# SCH_interrupt-proof-of-concept_2025-12-1.net
KiCad netlist of a schematic drawn in EasyEDA
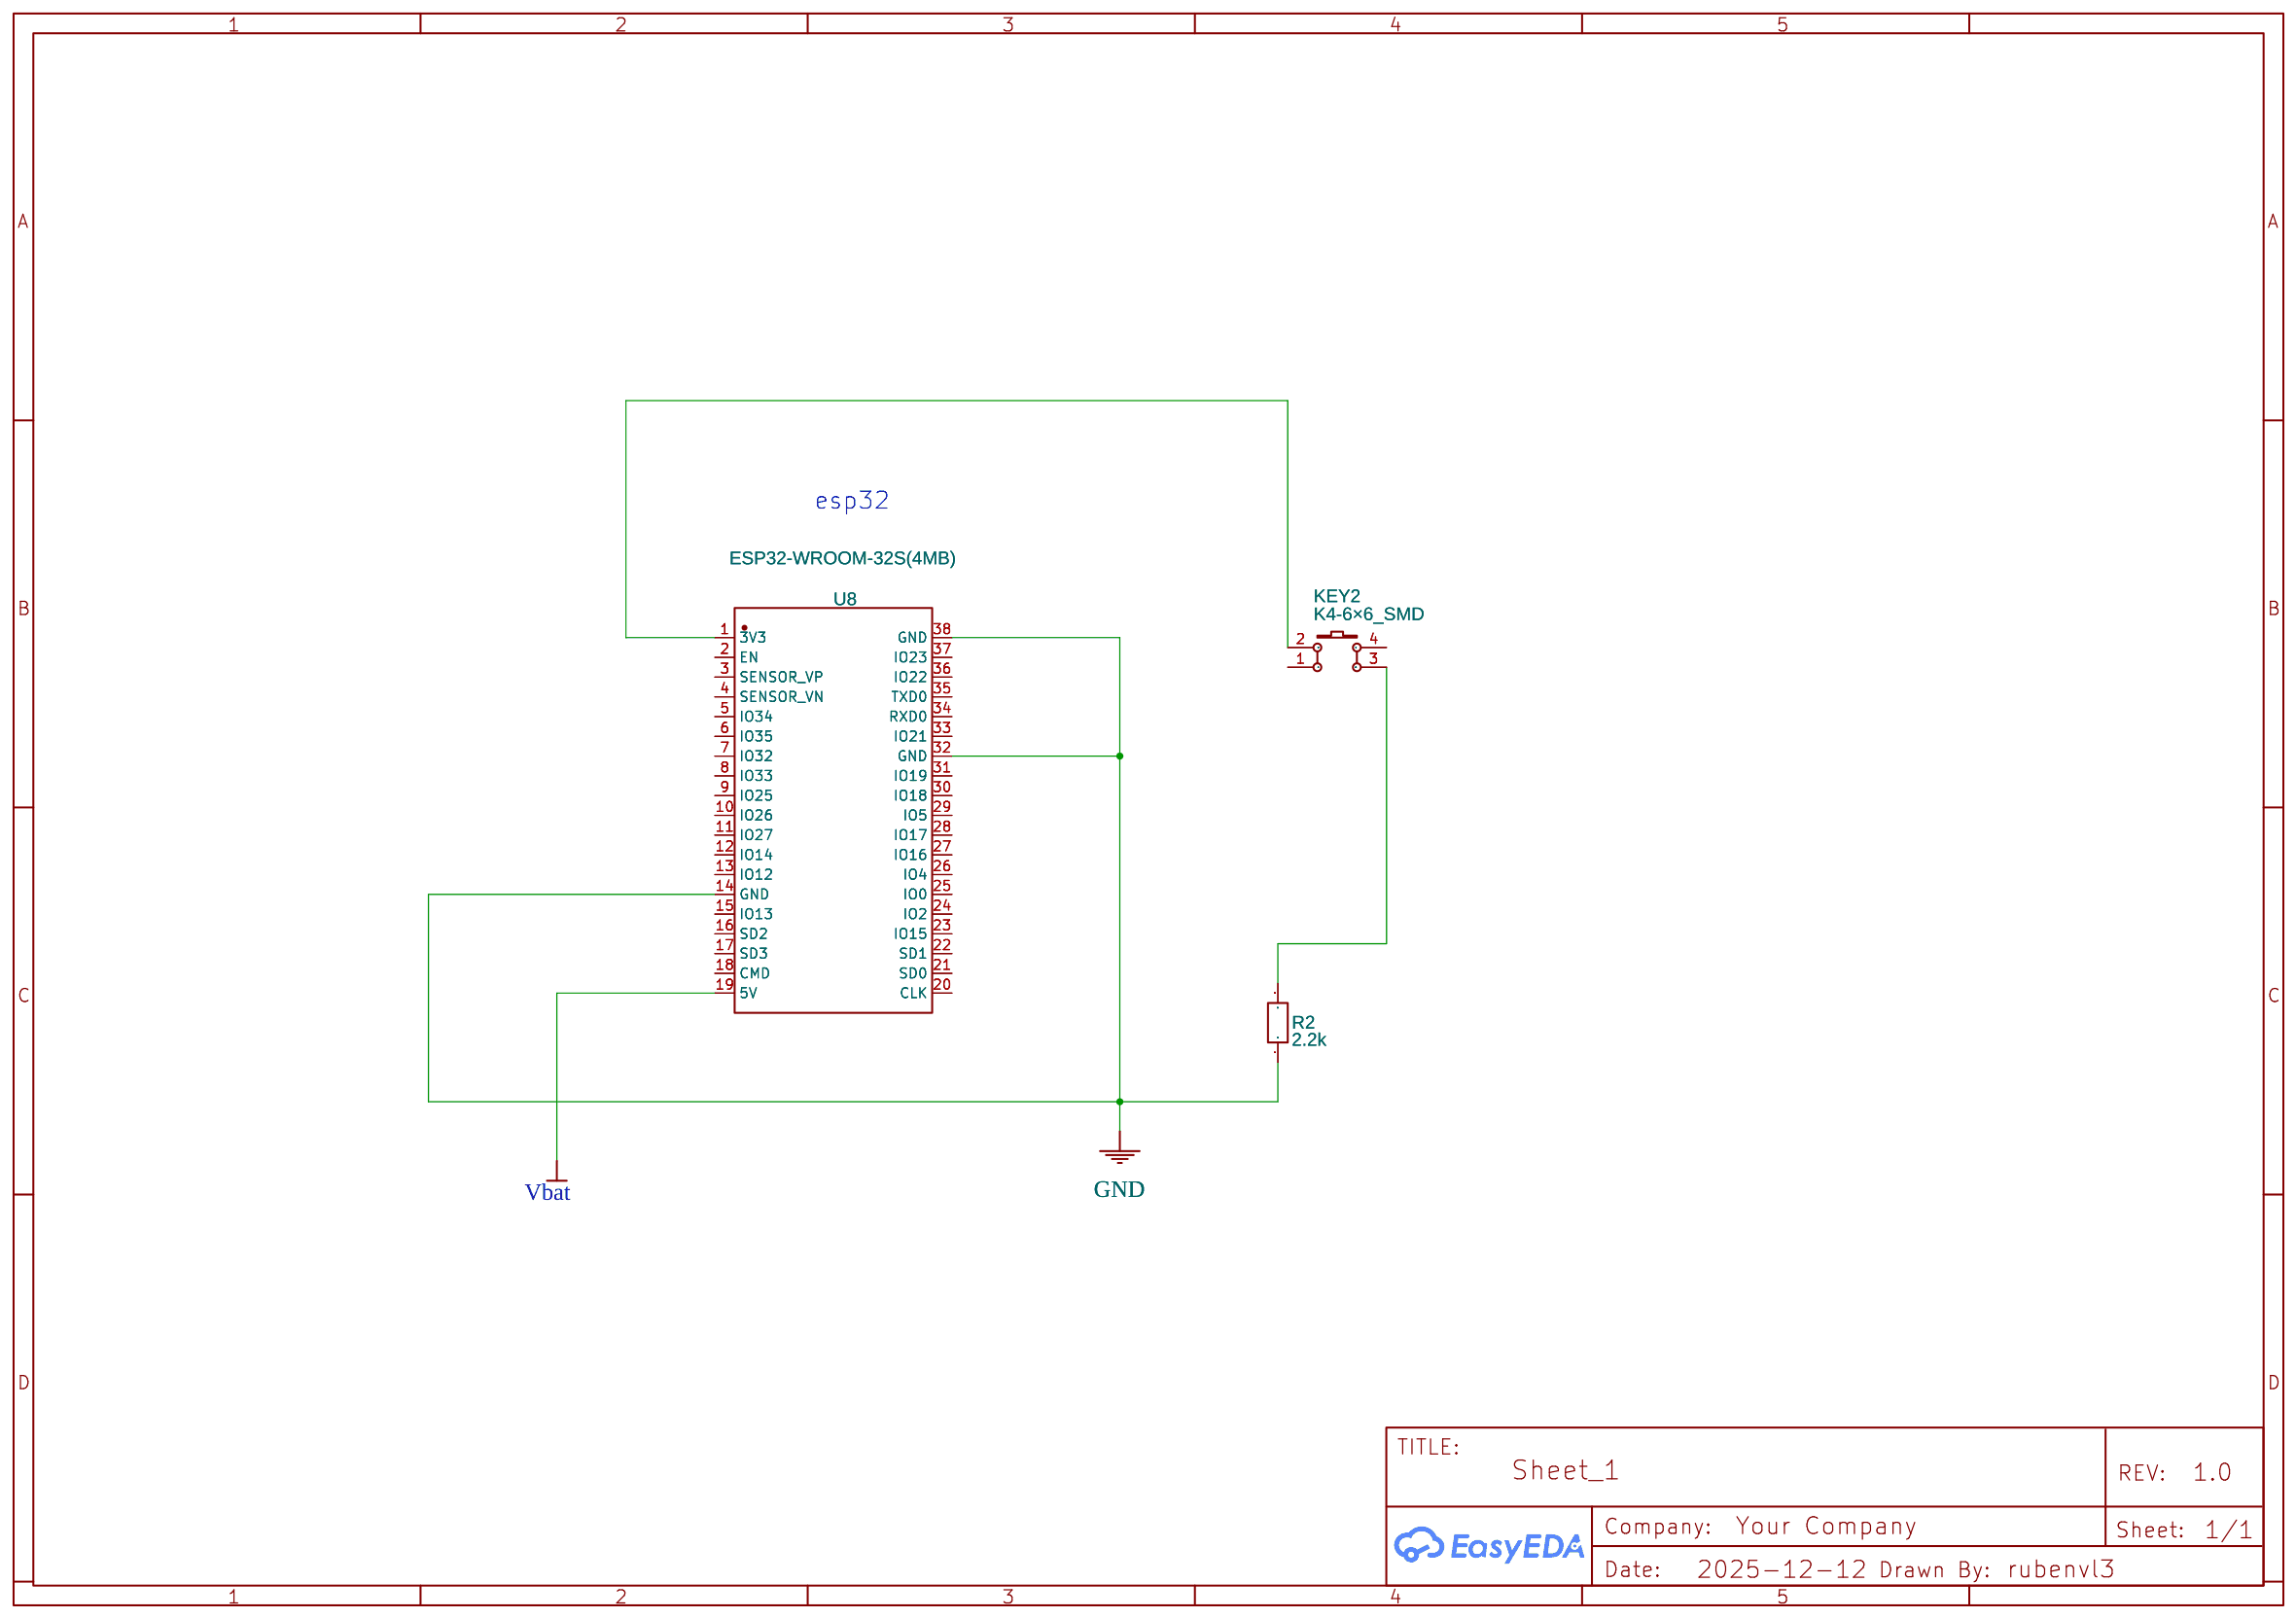
[diagram p0: schematic sheet]

(export (version "E")
  (design (tool "Eeschema 10.0.6"))
  (components
    (comp (ref "KEY2")
      (value "K4-6×6_SMD")
      (fields (field (name "Manufacturer Part") "K2-6639SP-D4SC-04") (field (name "Manufacturer") "韩国韩荣"))
      (libsource (lib "") (part "K4-6×6_SMD"))
    )
    (comp (ref "R2") (value "2.2k") (libsource (lib "") (part "R_0805_EU")))
    (comp (ref "U8")
      (value "ESP32-WROOM-32S(4MB)")
      (fields (field (name "Manufacturer") "Espressif Systems"))
      (libsource (lib "") (part "ESP32-WROOM-32S(4MB)"))
    )
  )
  (nets
    (net (code "1") (name "GND") (class "Default")
      (node (ref "R2") (pin "1") (pinfunction "1_1") (pintype "unspecified"))
      (node (ref "U8") (pin "14") (pinfunction "GND_14") (pintype "unspecified"))
      (node (ref "U8") (pin "32") (pinfunction "GND_32") (pintype "unspecified"))
      (node (ref "U8") (pin "38") (pinfunction "GND_38") (pintype "unspecified"))
    )
    (net (code "2") (name "Net-(KEY2-Pad3)") (class "Default")
      (node (ref "KEY2") (pin "3") (pinfunction "3_3") (pintype "unspecified"))
      (node (ref "R2") (pin "2") (pinfunction "2_2") (pintype "unspecified"))
    )
    (net (code "3") (name "Net-(U8-3V3)") (class "Default")
      (node (ref "KEY2") (pin "2") (pinfunction "2_2") (pintype "unspecified"))
      (node (ref "U8") (pin "1") (pinfunction "3V3_1") (pintype "unspecified"))
    )
    (net (code "4") (name "Vbat") (class "Default")
      (node (ref "U8") (pin "19") (pinfunction "5V_19") (pintype "unspecified"))
    )
    (net (code "5") (name "unconnected-(KEY2-Pad1)") (class "Default")
      (node (ref "KEY2") (pin "1") (pinfunction "1_1") (pintype "unspecified"))
    )
    (net (code "6") (name "unconnected-(KEY2-Pad4)") (class "Default")
      (node (ref "KEY2") (pin "4") (pinfunction "4_4") (pintype "unspecified"))
    )
    (net (code "7") (name "unconnected-(U8-CLK-Pad20)") (class "Default")
      (node (ref "U8") (pin "20") (pinfunction "CLK_20") (pintype "unspecified"))
    )
    (net (code "8") (name "unconnected-(U8-CMD-Pad18)") (class "Default")
      (node (ref "U8") (pin "18") (pinfunction "CMD_18") (pintype "unspecified"))
    )
    (net (code "9") (name "unconnected-(U8-EN-Pad2)") (class "Default")
      (node (ref "U8") (pin "2") (pinfunction "EN_2") (pintype "unspecified"))
    )
    (net (code "10") (name "unconnected-(U8-IO0-Pad25)") (class "Default")
      (node (ref "U8") (pin "25") (pinfunction "IO0_25") (pintype "unspecified"))
    )
    (net (code "11") (name "unconnected-(U8-IO2-Pad24)") (class "Default")
      (node (ref "U8") (pin "24") (pinfunction "IO2_24") (pintype "unspecified"))
    )
    (net (code "12") (name "unconnected-(U8-IO4-Pad26)") (class "Default")
      (node (ref "U8") (pin "26") (pinfunction "IO4_26") (pintype "unspecified"))
    )
    (net (code "13") (name "unconnected-(U8-IO5-Pad29)") (class "Default")
      (node (ref "U8") (pin "29") (pinfunction "IO5_29") (pintype "unspecified"))
    )
    (net (code "14") (name "unconnected-(U8-IO12-Pad13)") (class "Default")
      (node (ref "U8") (pin "13") (pinfunction "IO12_13") (pintype "unspecified"))
    )
    (net (code "15") (name "unconnected-(U8-IO13-Pad15)") (class "Default")
      (node (ref "U8") (pin "15") (pinfunction "IO13_15") (pintype "unspecified"))
    )
    (net (code "16") (name "unconnected-(U8-IO14-Pad12)") (class "Default")
      (node (ref "U8") (pin "12") (pinfunction "IO14_12") (pintype "unspecified"))
    )
    (net (code "17") (name "unconnected-(U8-IO15-Pad23)") (class "Default")
      (node (ref "U8") (pin "23") (pinfunction "IO15_23") (pintype "unspecified"))
    )
    (net (code "18") (name "unconnected-(U8-IO16-Pad27)") (class "Default")
      (node (ref "U8") (pin "27") (pinfunction "IO16_27") (pintype "unspecified"))
    )
    (net (code "19") (name "unconnected-(U8-IO17-Pad28)") (class "Default")
      (node (ref "U8") (pin "28") (pinfunction "IO17_28") (pintype "unspecified"))
    )
    (net (code "20") (name "unconnected-(U8-IO18-Pad30)") (class "Default")
      (node (ref "U8") (pin "30") (pinfunction "IO18_30") (pintype "unspecified"))
    )
    (net (code "21") (name "unconnected-(U8-IO19-Pad31)") (class "Default")
      (node (ref "U8") (pin "31") (pinfunction "IO19_31") (pintype "unspecified"))
    )
    (net (code "22") (name "unconnected-(U8-IO21-Pad33)") (class "Default")
      (node (ref "U8") (pin "33") (pinfunction "IO21_33") (pintype "unspecified"))
    )
    (net (code "23") (name "unconnected-(U8-IO22-Pad36)") (class "Default")
      (node (ref "U8") (pin "36") (pinfunction "IO22_36") (pintype "unspecified"))
    )
    (net (code "24") (name "unconnected-(U8-IO23-Pad37)") (class "Default")
      (node (ref "U8") (pin "37") (pinfunction "IO23_37") (pintype "unspecified"))
    )
    (net (code "25") (name "unconnected-(U8-IO25-Pad9)") (class "Default")
      (node (ref "U8") (pin "9") (pinfunction "IO25_9") (pintype "unspecified"))
    )
    (net (code "26") (name "unconnected-(U8-IO26-Pad10)") (class "Default")
      (node (ref "U8") (pin "10") (pinfunction "IO26_10") (pintype "unspecified"))
    )
    (net (code "27") (name "unconnected-(U8-IO27-Pad11)") (class "Default")
      (node (ref "U8") (pin "11") (pinfunction "IO27_11") (pintype "unspecified"))
    )
    (net (code "28") (name "unconnected-(U8-IO32-Pad7)") (class "Default")
      (node (ref "U8") (pin "7") (pinfunction "IO32_7") (pintype "unspecified"))
    )
    (net (code "29") (name "unconnected-(U8-IO33-Pad8)") (class "Default")
      (node (ref "U8") (pin "8") (pinfunction "IO33_8") (pintype "unspecified"))
    )
    (net (code "30") (name "unconnected-(U8-IO34-Pad5)") (class "Default")
      (node (ref "U8") (pin "5") (pinfunction "IO34_5") (pintype "unspecified"))
    )
    (net (code "31") (name "unconnected-(U8-IO35-Pad6)") (class "Default")
      (node (ref "U8") (pin "6") (pinfunction "IO35_6") (pintype "unspecified"))
    )
    (net (code "32") (name "unconnected-(U8-RXD0-Pad34)") (class "Default")
      (node (ref "U8") (pin "34") (pinfunction "RXD0_34") (pintype "unspecified"))
    )
    (net (code "33") (name "unconnected-(U8-SD0-Pad21)") (class "Default")
      (node (ref "U8") (pin "21") (pinfunction "SD0_21") (pintype "unspecified"))
    )
    (net (code "34") (name "unconnected-(U8-SD1-Pad22)") (class "Default")
      (node (ref "U8") (pin "22") (pinfunction "SD1_22") (pintype "unspecified"))
    )
    (net (code "35") (name "unconnected-(U8-SD2-Pad16)") (class "Default")
      (node (ref "U8") (pin "16") (pinfunction "SD2_16") (pintype "unspecified"))
    )
    (net (code "36") (name "unconnected-(U8-SD3-Pad17)") (class "Default")
      (node (ref "U8") (pin "17") (pinfunction "SD3_17") (pintype "unspecified"))
    )
    (net (code "37") (name "unconnected-(U8-SENSOR_VN-Pad4)") (class "Default")
      (node (ref "U8") (pin "4") (pinfunction "SENSOR_VN_4") (pintype "unspecified"))
    )
    (net (code "38") (name "unconnected-(U8-SENSOR_VP-Pad3)") (class "Default")
      (node (ref "U8") (pin "3") (pinfunction "SENSOR_VP_3") (pintype "unspecified"))
    )
    (net (code "39") (name "unconnected-(U8-TXD0-Pad35)") (class "Default")
      (node (ref "U8") (pin "35") (pinfunction "TXD0_35") (pintype "unspecified"))
    )
  )
)
